# pena.net
KiCad netlist of a schematic drawn in EAGLE
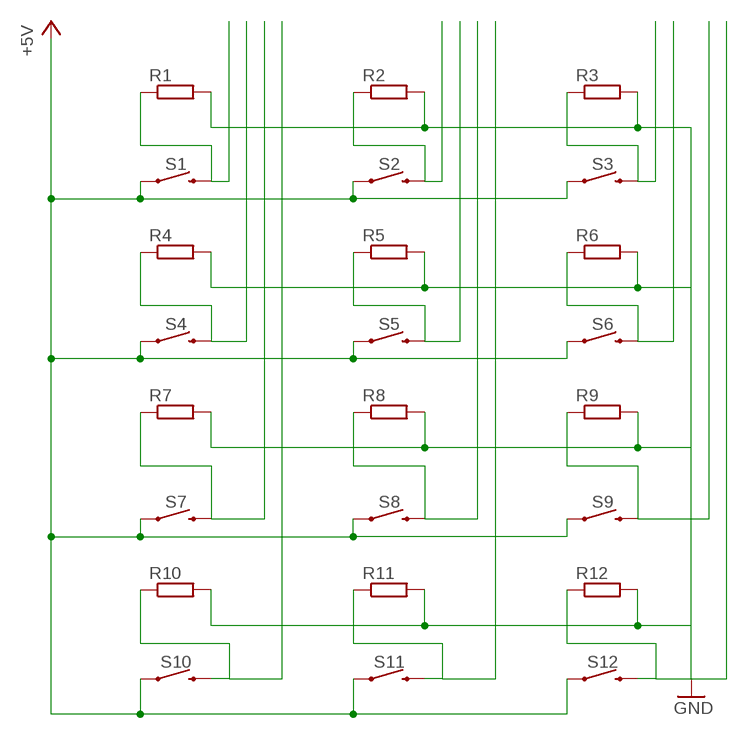
[diagram p0: schematic, sheet 1]

(export (version "E")
  (design (tool "Eeschema 10.0.6"))
  (components
    (comp (ref "R1")
      (value "R-EU_0207/10")
      (footprint "eagle-import:0207_10")
      (libsource (lib "eagle-import") (part "R-EU_0207/10"))
    )
    (comp (ref "R2")
      (value "R-EU_0207/10")
      (footprint "eagle-import:0207_10")
      (libsource (lib "eagle-import") (part "R-EU_0207/10"))
    )
    (comp (ref "R3")
      (value "R-EU_0207/10")
      (footprint "eagle-import:0207_10")
      (libsource (lib "eagle-import") (part "R-EU_0207/10"))
    )
    (comp (ref "R4")
      (value "R-EU_0207/10")
      (footprint "eagle-import:0207_10")
      (libsource (lib "eagle-import") (part "R-EU_0207/10"))
    )
    (comp (ref "R5")
      (value "R-EU_0207/10")
      (footprint "eagle-import:0207_10")
      (libsource (lib "eagle-import") (part "R-EU_0207/10"))
    )
    (comp (ref "R6")
      (value "R-EU_0207/10")
      (footprint "eagle-import:0207_10")
      (libsource (lib "eagle-import") (part "R-EU_0207/10"))
    )
    (comp (ref "R7")
      (value "R-EU_0207/10")
      (footprint "eagle-import:0207_10")
      (libsource (lib "eagle-import") (part "R-EU_0207/10"))
    )
    (comp (ref "R8")
      (value "R-EU_0207/10")
      (footprint "eagle-import:0207_10")
      (libsource (lib "eagle-import") (part "R-EU_0207/10"))
    )
    (comp (ref "R9")
      (value "R-EU_0207/10")
      (footprint "eagle-import:0207_10")
      (libsource (lib "eagle-import") (part "R-EU_0207/10"))
    )
    (comp (ref "R10")
      (value "R-EU_0207/10")
      (footprint "eagle-import:0207_10")
      (libsource (lib "eagle-import") (part "R-EU_0207/10"))
    )
    (comp (ref "R11")
      (value "R-EU_0207/10")
      (footprint "eagle-import:0207_10")
      (libsource (lib "eagle-import") (part "R-EU_0207/10"))
    )
    (comp (ref "R12")
      (value "R-EU_0207/10")
      (footprint "eagle-import:0207_10")
      (libsource (lib "eagle-import") (part "R-EU_0207/10"))
    )
    (comp (ref "S1")
      (value "MOMENTARY-SWITCH-SPST-SMD-6.2MM-TALL")
      (footprint "eagle-import:TACTILE_SWITCH_SMD_6.2MM_TALL")
      (libsource (lib "eagle-import") (part "MOMENTARY-SWITCH-SPST-SMD-6.2MM-TALL"))
    )
    (comp (ref "S2")
      (value "MOMENTARY-SWITCH-SPST-SMD-6.2MM-TALL")
      (footprint "eagle-import:TACTILE_SWITCH_SMD_6.2MM_TALL")
      (libsource (lib "eagle-import") (part "MOMENTARY-SWITCH-SPST-SMD-6.2MM-TALL"))
    )
    (comp (ref "S3")
      (value "MOMENTARY-SWITCH-SPST-SMD-6.2MM-TALL")
      (footprint "eagle-import:TACTILE_SWITCH_SMD_6.2MM_TALL")
      (libsource (lib "eagle-import") (part "MOMENTARY-SWITCH-SPST-SMD-6.2MM-TALL"))
    )
    (comp (ref "S4")
      (value "MOMENTARY-SWITCH-SPST-SMD-6.2MM-TALL")
      (footprint "eagle-import:TACTILE_SWITCH_SMD_6.2MM_TALL")
      (libsource (lib "eagle-import") (part "MOMENTARY-SWITCH-SPST-SMD-6.2MM-TALL"))
    )
    (comp (ref "S5")
      (value "MOMENTARY-SWITCH-SPST-SMD-6.2MM-TALL")
      (footprint "eagle-import:TACTILE_SWITCH_SMD_6.2MM_TALL")
      (libsource (lib "eagle-import") (part "MOMENTARY-SWITCH-SPST-SMD-6.2MM-TALL"))
    )
    (comp (ref "S6")
      (value "MOMENTARY-SWITCH-SPST-SMD-6.2MM-TALL")
      (footprint "eagle-import:TACTILE_SWITCH_SMD_6.2MM_TALL")
      (libsource (lib "eagle-import") (part "MOMENTARY-SWITCH-SPST-SMD-6.2MM-TALL"))
    )
    (comp (ref "S7")
      (value "MOMENTARY-SWITCH-SPST-SMD-6.2MM-TALL")
      (footprint "eagle-import:TACTILE_SWITCH_SMD_6.2MM_TALL")
      (libsource (lib "eagle-import") (part "MOMENTARY-SWITCH-SPST-SMD-6.2MM-TALL"))
    )
    (comp (ref "S8")
      (value "MOMENTARY-SWITCH-SPST-SMD-6.2MM-TALL")
      (footprint "eagle-import:TACTILE_SWITCH_SMD_6.2MM_TALL")
      (libsource (lib "eagle-import") (part "MOMENTARY-SWITCH-SPST-SMD-6.2MM-TALL"))
    )
    (comp (ref "S9")
      (value "MOMENTARY-SWITCH-SPST-SMD-6.2MM-TALL")
      (footprint "eagle-import:TACTILE_SWITCH_SMD_6.2MM_TALL")
      (libsource (lib "eagle-import") (part "MOMENTARY-SWITCH-SPST-SMD-6.2MM-TALL"))
    )
    (comp (ref "S10")
      (value "MOMENTARY-SWITCH-SPST-SMD-6.2MM-TALL")
      (footprint "eagle-import:TACTILE_SWITCH_SMD_6.2MM_TALL")
      (libsource (lib "eagle-import") (part "MOMENTARY-SWITCH-SPST-SMD-6.2MM-TALL"))
    )
    (comp (ref "S11")
      (value "MOMENTARY-SWITCH-SPST-SMD-6.2MM-TALL")
      (footprint "eagle-import:TACTILE_SWITCH_SMD_6.2MM_TALL")
      (libsource (lib "eagle-import") (part "MOMENTARY-SWITCH-SPST-SMD-6.2MM-TALL"))
    )
    (comp (ref "S12")
      (value "MOMENTARY-SWITCH-SPST-SMD-6.2MM-TALL")
      (footprint "eagle-import:TACTILE_SWITCH_SMD_6.2MM_TALL")
      (libsource (lib "eagle-import") (part "MOMENTARY-SWITCH-SPST-SMD-6.2MM-TALL"))
    )
  )
  (nets
    (net (code "1") (name "+5V") (class "Default")
      (node (ref "S1") (pin "A2") (pinfunction "1_A2") (pintype "passive"))
      (node (ref "S10") (pin "A2") (pinfunction "1_A2") (pintype "passive"))
      (node (ref "S11") (pin "A2") (pinfunction "1_A2") (pintype "passive"))
      (node (ref "S12") (pin "A2") (pinfunction "1_A2") (pintype "passive"))
      (node (ref "S2") (pin "A2") (pinfunction "1_A2") (pintype "passive"))
      (node (ref "S3") (pin "A2") (pinfunction "1_A2") (pintype "passive"))
      (node (ref "S4") (pin "A2") (pinfunction "1_A2") (pintype "passive"))
      (node (ref "S5") (pin "A2") (pinfunction "1_A2") (pintype "passive"))
      (node (ref "S6") (pin "A2") (pinfunction "1_A2") (pintype "passive"))
      (node (ref "S7") (pin "A2") (pinfunction "1_A2") (pintype "passive"))
      (node (ref "S8") (pin "A2") (pinfunction "1_A2") (pintype "passive"))
      (node (ref "S9") (pin "A2") (pinfunction "1_A2") (pintype "passive"))
    )
    (net (code "2") (name "GND") (class "Default")
      (node (ref "R1") (pin "2") (pinfunction "2_2") (pintype "passive"))
      (node (ref "R10") (pin "2") (pinfunction "2_2") (pintype "passive"))
      (node (ref "R11") (pin "2") (pinfunction "2_2") (pintype "passive"))
      (node (ref "R12") (pin "2") (pinfunction "2_2") (pintype "passive"))
      (node (ref "R2") (pin "2") (pinfunction "2_2") (pintype "passive"))
      (node (ref "R3") (pin "2") (pinfunction "2_2") (pintype "passive"))
      (node (ref "R4") (pin "2") (pinfunction "2_2") (pintype "passive"))
      (node (ref "R5") (pin "2") (pinfunction "2_2") (pintype "passive"))
      (node (ref "R6") (pin "2") (pinfunction "2_2") (pintype "passive"))
      (node (ref "R7") (pin "2") (pinfunction "2_2") (pintype "passive"))
      (node (ref "R8") (pin "2") (pinfunction "2_2") (pintype "passive"))
      (node (ref "R9") (pin "2") (pinfunction "2_2") (pintype "passive"))
    )
    (net (code "3") (name "Net-(S1-2)") (class "Default")
      (node (ref "R1") (pin "1") (pinfunction "1_1") (pintype "passive"))
      (node (ref "S1") (pin "B2") (pinfunction "2_B2") (pintype "passive"))
    )
    (net (code "4") (name "Net-(S2-2)") (class "Default")
      (node (ref "R2") (pin "1") (pinfunction "1_1") (pintype "passive"))
      (node (ref "S2") (pin "B2") (pinfunction "2_B2") (pintype "passive"))
    )
    (net (code "5") (name "Net-(S3-2)") (class "Default")
      (node (ref "R3") (pin "1") (pinfunction "1_1") (pintype "passive"))
      (node (ref "S3") (pin "B2") (pinfunction "2_B2") (pintype "passive"))
    )
    (net (code "6") (name "Net-(S4-2)") (class "Default")
      (node (ref "R4") (pin "1") (pinfunction "1_1") (pintype "passive"))
      (node (ref "S4") (pin "B2") (pinfunction "2_B2") (pintype "passive"))
    )
    (net (code "7") (name "Net-(S5-2)") (class "Default")
      (node (ref "R5") (pin "1") (pinfunction "1_1") (pintype "passive"))
      (node (ref "S5") (pin "B2") (pinfunction "2_B2") (pintype "passive"))
    )
    (net (code "8") (name "Net-(S6-2)") (class "Default")
      (node (ref "R6") (pin "1") (pinfunction "1_1") (pintype "passive"))
      (node (ref "S6") (pin "B2") (pinfunction "2_B2") (pintype "passive"))
    )
    (net (code "9") (name "Net-(S7-2)") (class "Default")
      (node (ref "R7") (pin "1") (pinfunction "1_1") (pintype "passive"))
      (node (ref "S7") (pin "B2") (pinfunction "2_B2") (pintype "passive"))
    )
    (net (code "10") (name "Net-(S8-2)") (class "Default")
      (node (ref "R8") (pin "1") (pinfunction "1_1") (pintype "passive"))
      (node (ref "S8") (pin "B2") (pinfunction "2_B2") (pintype "passive"))
    )
    (net (code "11") (name "Net-(S9-2)") (class "Default")
      (node (ref "R9") (pin "1") (pinfunction "1_1") (pintype "passive"))
      (node (ref "S9") (pin "B2") (pinfunction "2_B2") (pintype "passive"))
    )
    (net (code "12") (name "Net-(S10-2)") (class "Default")
      (node (ref "R10") (pin "1") (pinfunction "1_1") (pintype "passive"))
      (node (ref "S10") (pin "B2") (pinfunction "2_B2") (pintype "passive"))
    )
    (net (code "13") (name "Net-(S11-2)") (class "Default")
      (node (ref "R11") (pin "1") (pinfunction "1_1") (pintype "passive"))
      (node (ref "S11") (pin "B2") (pinfunction "2_B2") (pintype "passive"))
    )
    (net (code "14") (name "Net-(S12-2)") (class "Default")
      (node (ref "R12") (pin "1") (pinfunction "1_1") (pintype "passive"))
      (node (ref "S12") (pin "B2") (pinfunction "2_B2") (pintype "passive"))
    )
  )
)
